# WG-JW-MB.net
KiCad netlist of a schematic drawn in Altium Designer
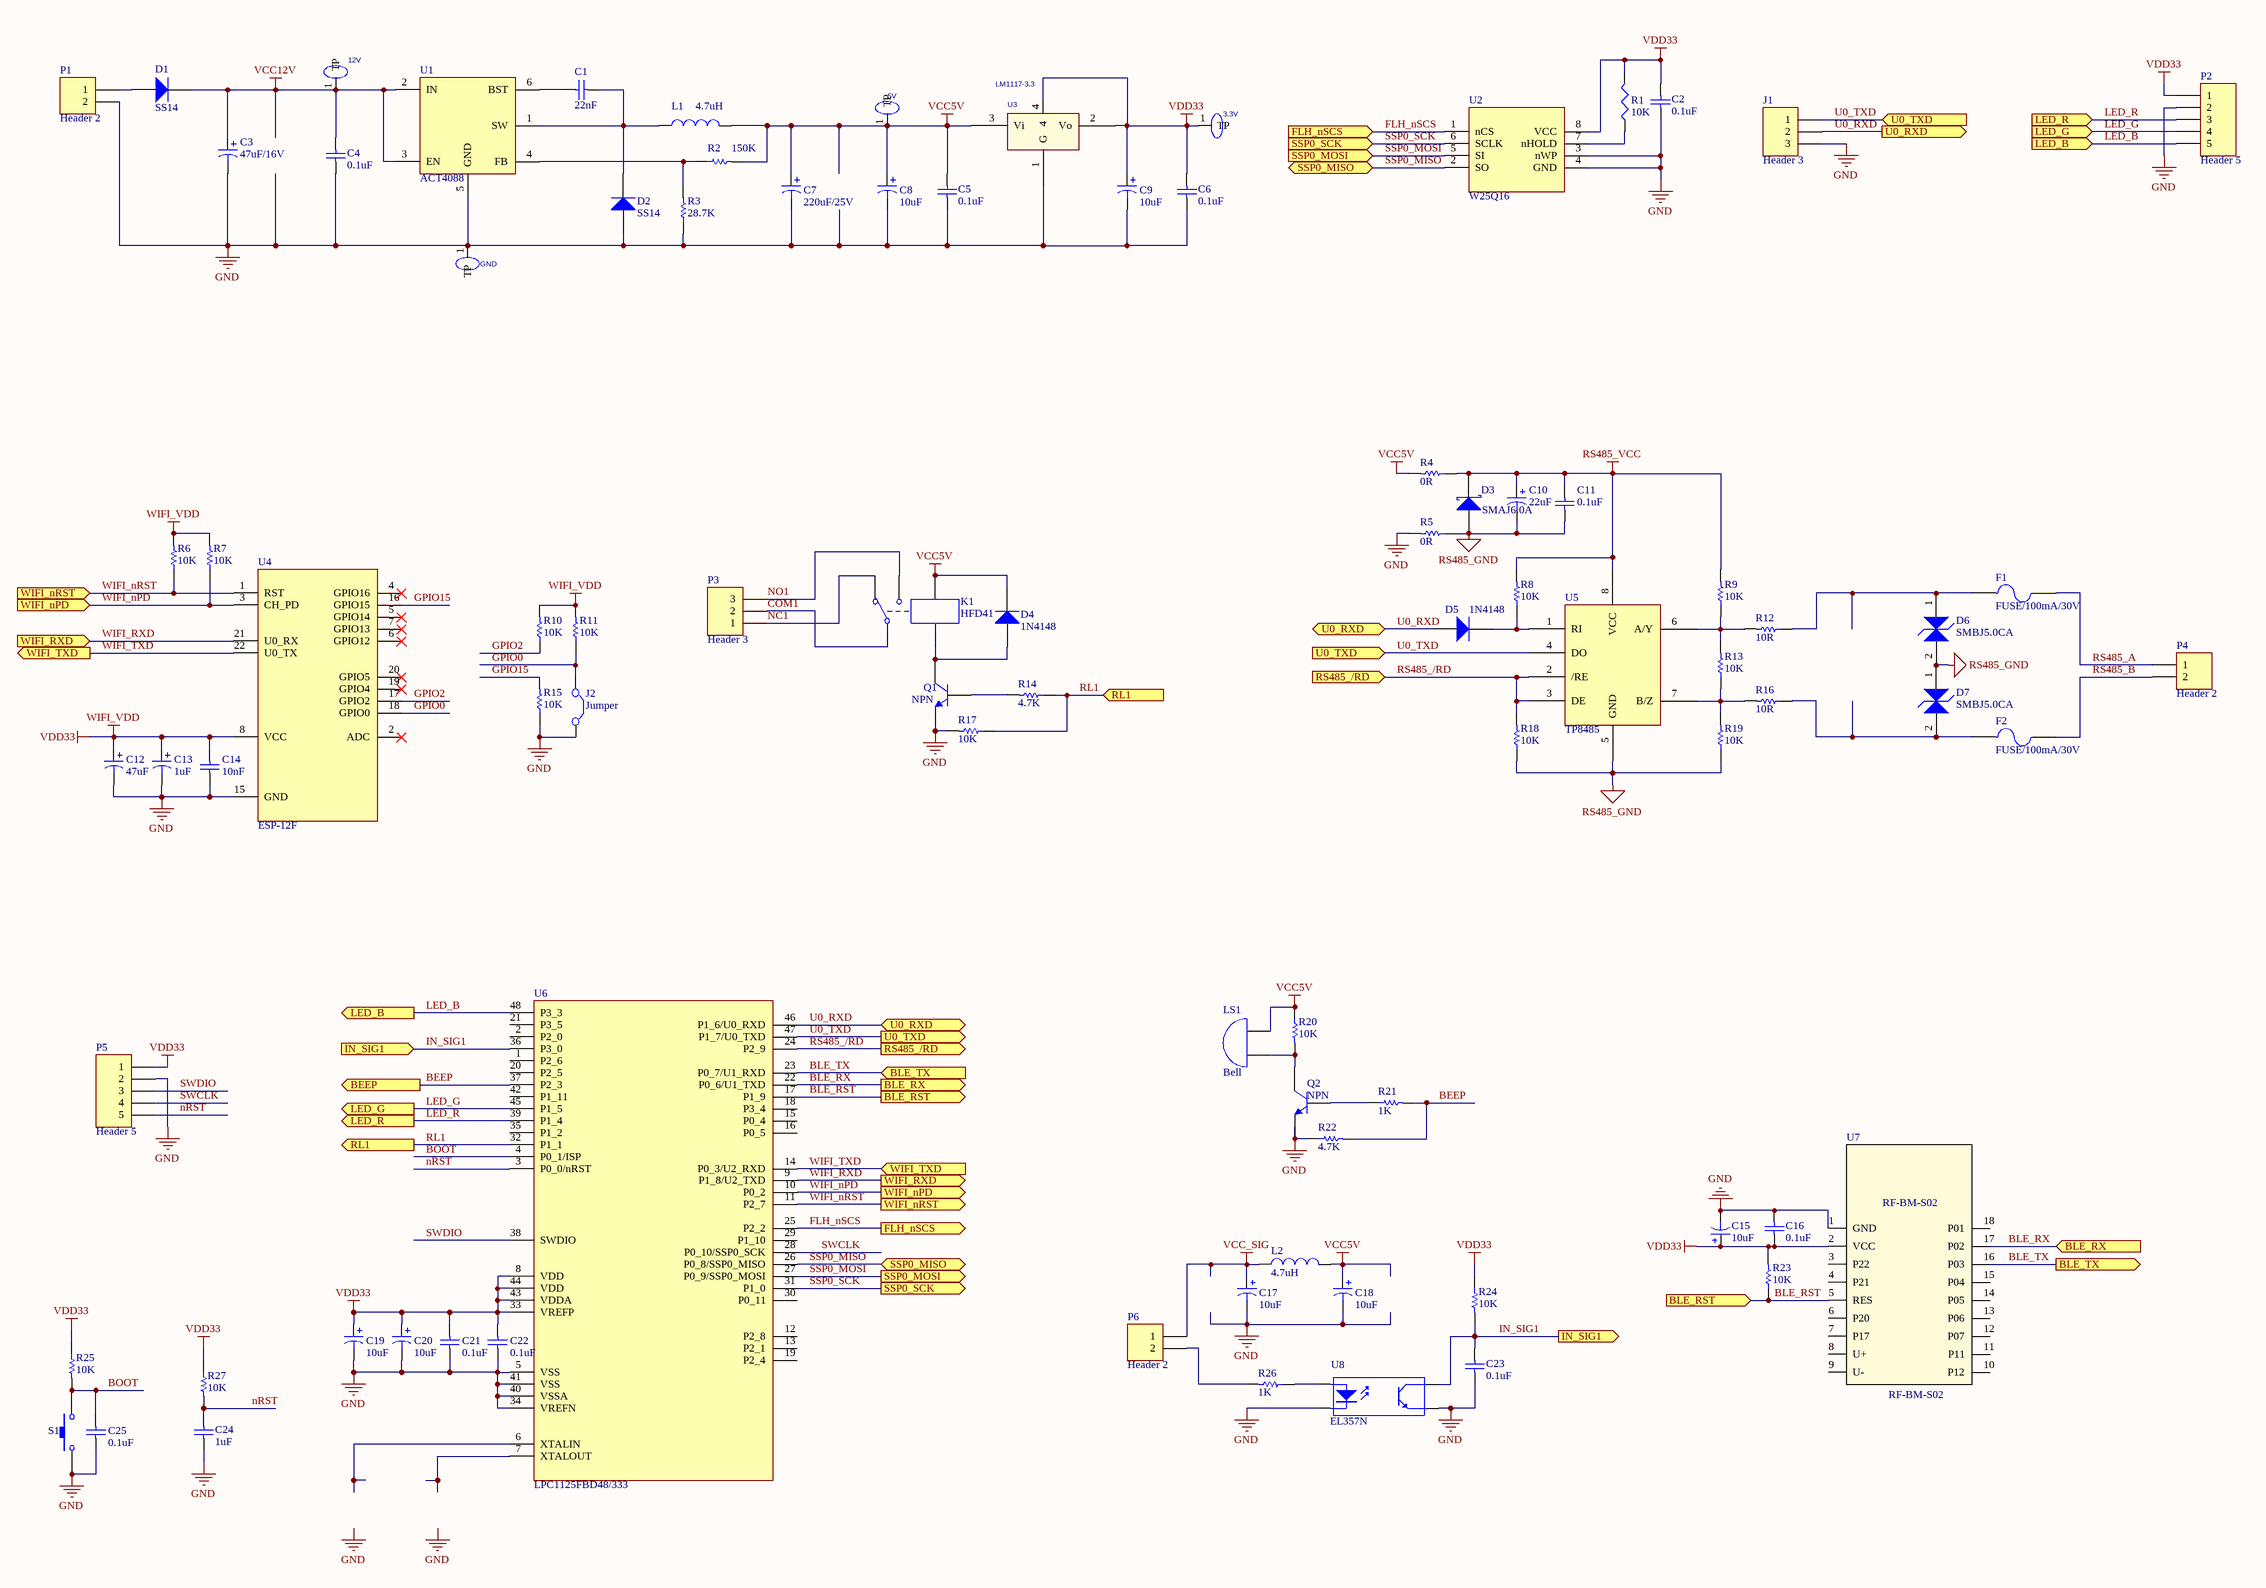
[diagram p0: WG-JW-MB.SchDoc]

(export (version "E")
  (design (tool "Eeschema 10.0.6"))
  (components
    (comp (ref "3.3V") (value "5VOUT") (libsource (lib "*") (part "TESTPOINT")))
    (comp (ref "5V") (value "5VOUT") (libsource (lib "*") (part "TESTPOINT")))
    (comp (ref "12V") (value "5VOUT") (libsource (lib "*") (part "TESTPOINT")))
    (comp (ref "C1")
      (value "22nF")
      (footprint "0805 - C")
      (description "Capacitor")
      (fields (field (name "PUBLISHER") "Altium Limited"))
      (libsource (lib "Miscellaneous Devices") (part "Cap"))
    )
    (comp (ref "C2")
      (value "0.1uF")
      (footprint "0805 - C")
      (description "Capacitor")
      (fields (field (name "PUBLISHER") "Altium Limited"))
      (libsource (lib "Miscellaneous Devices") (part "Cap"))
    )
    (comp (ref "C3")
      (value "47uF/16V")
      (footprint "smd_ec_d5.2")
      (description "Polarized Capacitor (Radial)")
      (fields (field (name "PUBLISHER") "Altium Limited"))
      (libsource (lib "Miscellaneous Devices") (part "Cap Pol1"))
    )
    (comp (ref "C4")
      (value "0.1uF")
      (footprint "0805 - C")
      (description "Capacitor")
      (fields (field (name "PUBLISHER") "Altium Limited"))
      (libsource (lib "Miscellaneous Devices") (part "Cap"))
    )
    (comp (ref "C5")
      (value "0.1uF")
      (footprint "0805 - C")
      (description "Capacitor")
      (fields (field (name "PUBLISHER") "Altium Limited"))
      (libsource (lib "Miscellaneous Devices") (part "Cap"))
    )
    (comp (ref "C6")
      (value "0.1uF")
      (footprint "0805 - C")
      (description "Capacitor")
      (fields (field (name "PUBLISHER") "Altium Limited"))
      (libsource (lib "Miscellaneous Devices") (part "Cap"))
    )
    (comp (ref "C7")
      (value "220uF/25V")
      (footprint "smd_ec_d8")
      (description "Polarized Capacitor (Radial)")
      (fields (field (name "PUBLISHER") "Altium Limited"))
      (libsource (lib "Miscellaneous Devices") (part "Cap Pol1"))
    )
    (comp (ref "C8")
      (value "10uF")
      (footprint "0805 - C")
      (description "Polarized Capacitor (Radial)")
      (fields (field (name "PUBLISHER") "Altium Limited"))
      (libsource (lib "Miscellaneous Devices") (part "Cap Pol1"))
    )
    (comp (ref "C9")
      (value "10uF")
      (footprint "0805 - C")
      (description "Polarized Capacitor (Radial)")
      (fields (field (name "PUBLISHER") "Altium Limited"))
      (libsource (lib "Miscellaneous Devices") (part "Cap Pol1"))
    )
    (comp (ref "C10")
      (value "22uF")
      (footprint "0805 - C")
      (description "Polarized Capacitor (Radial)")
      (fields (field (name "PUBLISHER") "Altium Limited"))
      (libsource (lib "Miscellaneous Devices") (part "Cap Pol1"))
    )
    (comp (ref "C11")
      (value "0.1uF")
      (footprint "0805 - C")
      (description "Capacitor")
      (fields (field (name "PUBLISHER") "Altium Limited"))
      (libsource (lib "Miscellaneous Devices") (part "Cap"))
    )
    (comp (ref "C12")
      (value "47uF")
      (footprint "SMD_EC_D5.2")
      (description "Polarized Capacitor (Radial)")
      (fields (field (name "PUBLISHER") "Altium Limited"))
      (libsource (lib "Miscellaneous Devices") (part "Cap Pol1"))
    )
    (comp (ref "C13")
      (value "1uF")
      (footprint "0805 - C")
      (description "Polarized Capacitor (Radial)")
      (fields (field (name "PUBLISHER") "Altium Limited"))
      (libsource (lib "Miscellaneous Devices") (part "Cap Pol1"))
    )
    (comp (ref "C14")
      (value "10nF")
      (footprint "0805 - C")
      (description "Capacitor")
      (fields (field (name "PUBLISHER") "Altium Limited"))
      (libsource (lib "Miscellaneous Devices") (part "Cap"))
    )
    (comp (ref "C15")
      (value "10uF")
      (footprint "0805 - C")
      (description "Polarized Capacitor (Radial)")
      (fields (field (name "PUBLISHER") "Altium Limited"))
      (libsource (lib "Miscellaneous Devices") (part "Cap Pol1"))
    )
    (comp (ref "C16")
      (value "0.1uF")
      (footprint "0805 - C")
      (description "Capacitor")
      (fields (field (name "PUBLISHER") "Altium Limited"))
      (libsource (lib "Miscellaneous Devices") (part "Cap"))
    )
    (comp (ref "C17")
      (value "10uF")
      (footprint "0805 - C")
      (description "Polarized Capacitor (Radial)")
      (fields (field (name "PUBLISHER") "Altium Limited"))
      (libsource (lib "Miscellaneous Devices") (part "Cap Pol1"))
    )
    (comp (ref "C18")
      (value "10uF")
      (footprint "0805 - C")
      (description "Polarized Capacitor (Radial)")
      (fields (field (name "PUBLISHER") "Altium Limited"))
      (libsource (lib "Miscellaneous Devices") (part "Cap Pol1"))
    )
    (comp (ref "C19")
      (value "10uF")
      (footprint "0805 - C")
      (description "Polarized Capacitor (Radial)")
      (fields (field (name "PUBLISHER") "Altium Limited"))
      (libsource (lib "Miscellaneous Devices") (part "Cap Pol1"))
    )
    (comp (ref "C20")
      (value "10uF")
      (footprint "0805 - C")
      (description "Polarized Capacitor (Radial)")
      (fields (field (name "PUBLISHER") "Altium Limited"))
      (libsource (lib "Miscellaneous Devices") (part "Cap Pol1"))
    )
    (comp (ref "C21")
      (value "0.1uF")
      (footprint "0805 - C")
      (description "Capacitor")
      (fields (field (name "PUBLISHER") "Altium Limited"))
      (libsource (lib "Miscellaneous Devices") (part "Cap"))
    )
    (comp (ref "C22")
      (value "0.1uF")
      (footprint "0805 - C")
      (description "Capacitor")
      (fields (field (name "PUBLISHER") "Altium Limited"))
      (libsource (lib "Miscellaneous Devices") (part "Cap"))
    )
    (comp (ref "C23")
      (value "0.1uF")
      (footprint "0805 - C")
      (description "Capacitor")
      (fields (field (name "PUBLISHER") "Altium Limited"))
      (libsource (lib "Miscellaneous Devices") (part "Cap"))
    )
    (comp (ref "C24")
      (value "1uF")
      (footprint "0805 - C")
      (description "Capacitor")
      (fields (field (name "PUBLISHER") "Altium Limited"))
      (libsource (lib "Miscellaneous Devices") (part "Cap"))
    )
    (comp (ref "C25")
      (value "0.1uF")
      (footprint "0805 - C")
      (description "Capacitor")
      (fields (field (name "PUBLISHER") "Altium Limited"))
      (libsource (lib "Miscellaneous Devices") (part "Cap"))
    )
    (comp (ref "D1")
      (value "SS14")
      (footprint "SMD_DIODE_SMA")
      (description "Default Diode")
      (fields (field (name "PUBLISHER") "Altium Limited"))
      (libsource (lib "Miscellaneous Devices") (part "Diode"))
    )
    (comp (ref "D2")
      (value "SS14")
      (footprint "SMD_DIODE_SMA")
      (description "Default Diode")
      (fields (field (name "PUBLISHER") "Altium Limited"))
      (libsource (lib "Miscellaneous Devices") (part "Diode"))
    )
    (comp (ref "D3")
      (value "SMAJ6.0A")
      (footprint "SMAJ_A")
      (description "Schottky Diode")
      (fields (field (name "PUBLISHER") "Altium Limited"))
      (libsource (lib "Miscellaneous Devices") (part "D Schottky"))
    )
    (comp (ref "D4")
      (value "1N4148")
      (footprint "1n4148")
      (description "Default Diode")
      (fields (field (name "PUBLISHER") "Altium Limited"))
      (libsource (lib "Miscellaneous Devices") (part "Diode"))
    )
    (comp (ref "D5")
      (value "1N4148")
      (footprint "1n4148")
      (description "Default Diode")
      (fields (field (name "PUBLISHER") "Altium Limited"))
      (libsource (lib "Miscellaneous Devices") (part "Diode"))
    )
    (comp (ref "D6") (value "SMBJ5.0CA") (footprint "SMBJ_CA") (libsource (lib "Gsd") (part "TVS")))
    (comp (ref "D7") (value "SMBJ5.0CA") (footprint "SMBJ_CA") (libsource (lib "Gsd") (part "TVS")))
    (comp (ref "F1")
      (value "FUSE/100mA/30V")
      (footprint "SMD_POLYSWITCH")
      (description "Fuse")
      (fields (field (name "PUBLISHER") "Altium Limited"))
      (libsource (lib "Miscellaneous Devices") (part "Fuse 2"))
    )
    (comp (ref "F2")
      (value "FUSE/100mA/30V")
      (footprint "SMD_POLYSWITCH")
      (description "Fuse")
      (fields (field (name "PUBLISHER") "Altium Limited"))
      (libsource (lib "Miscellaneous Devices") (part "Fuse 2"))
    )
    (comp (ref "GND") (value "5VOUT") (libsource (lib "*") (part "TESTPOINT")))
    (comp (ref "J1")
      (value "Header 3")
      (footprint "HDR1X3")
      (description "Header, 3-Pin")
      (fields (field (name "PUBLISHER") "Altium Limited"))
      (libsource (lib "Miscellaneous Connectors") (part "Header 3"))
    )
    (comp (ref "J2")
      (value "Jumper")
      (footprint "HDR1X2")
      (description "Jumper Wire")
      (fields (field (name "PUBLISHER") "Altium Limited"))
      (libsource (lib "Miscellaneous Devices") (part "Jumper"))
    )
    (comp (ref "K1")
      (value "HFD41")
      (footprint "HFD23")
      (description "Single-Pole Dual-Throw Relay")
      (fields (field (name "PUBLISHER") "Altium Limited"))
      (libsource (lib "Miscellaneous Devices") (part "Relay-SPDT"))
    )
    (comp (ref "L1")
      (value "4.7uH")
      (footprint "SMD_L_3015")
      (description "Inductor")
      (fields (field (name "PUBLISHER") "Altium Limited"))
      (libsource (lib "Miscellaneous Devices") (part "Inductor"))
    )
    (comp (ref "L2")
      (value "4.7uH")
      (footprint "SMD_L_3015")
      (description "Inductor")
      (fields (field (name "PUBLISHER") "Altium Limited"))
      (libsource (lib "Miscellaneous Devices") (part "Inductor"))
    )
    (comp (ref "LS1")
      (value "Bell")
      (footprint "BZ_D12")
      (description "Electrical Bell")
      (fields (field (name "PUBLISHER") "Altium Limited"))
      (libsource (lib "Miscellaneous Devices") (part "Bell"))
    )
    (comp (ref "P1")
      (value "Header 2")
      (footprint "CON2-5.08")
      (description "Header, 2-Pin")
      (fields (field (name "PUBLISHER") "Altium Limited"))
      (libsource (lib "") (part "Header 2_1"))
    )
    (comp (ref "P2")
      (value "Header 5")
      (footprint "CN_1X5_P200")
      (description "Header, 5-Pin")
      (fields (field (name "PUBLISHER") "Altium Limited"))
      (libsource (lib "") (part "Header 5_1"))
    )
    (comp (ref "P3")
      (value "Header 3")
      (footprint "CN_1X3_P200")
      (description "Header, 3-Pin")
      (fields (field (name "PUBLISHER") "Altium Limited"))
      (libsource (lib "") (part "Header 3_1"))
    )
    (comp (ref "P4")
      (value "Header 2")
      (footprint "cn_1x2_p200")
      (description "Header, 2-Pin")
      (fields (field (name "PUBLISHER") "Altium Limited"))
      (libsource (lib "Miscellaneous Connectors") (part "Header 2"))
    )
    (comp (ref "P5")
      (value "Header 5")
      (footprint "CN_1X5_P200")
      (description "Header, 5-Pin")
      (fields (field (name "PUBLISHER") "Altium Limited"))
      (libsource (lib "Miscellaneous Connectors") (part "Header 5"))
    )
    (comp (ref "P6")
      (value "Header 2")
      (footprint "CN_1X2_P200")
      (description "Header, 2-Pin")
      (fields (field (name "PUBLISHER") "Altium Limited"))
      (libsource (lib "") (part "Header 2_1"))
    )
    (comp (ref "Q1")
      (value "NPN")
      (footprint "SOT23")
      (description "NPN Bipolar Transistor")
      (fields (field (name "PUBLISHER") "Altium Limited"))
      (libsource (lib "Miscellaneous Devices") (part "NPN"))
    )
    (comp (ref "Q2")
      (value "NPN")
      (footprint "SOT23")
      (description "NPN Bipolar Transistor")
      (fields (field (name "PUBLISHER") "Altium Limited"))
      (libsource (lib "Miscellaneous Devices") (part "NPN"))
    )
    (comp (ref "R1")
      (value "10K")
      (footprint "0805 - R")
      (description "Resistor")
      (fields (field (name "PUBLISHER") "Altium Limited"))
      (libsource (lib "Miscellaneous Devices") (part "Res3"))
    )
    (comp (ref "R2")
      (value "150K")
      (footprint "0805 - R")
      (description "Resistor")
      (fields (field (name "PUBLISHER") "Altium Limited"))
      (libsource (lib "Miscellaneous Devices") (part "Res1"))
    )
    (comp (ref "R3")
      (value "28.7K")
      (footprint "0805 - R")
      (description "Resistor")
      (fields (field (name "PUBLISHER") "Altium Limited"))
      (libsource (lib "Miscellaneous Devices") (part "Res1"))
    )
    (comp (ref "R4")
      (value "0R")
      (footprint "0805 - R")
      (description "Resistor")
      (fields (field (name "PUBLISHER") "Altium Limited"))
      (libsource (lib "Miscellaneous Devices") (part "Res1"))
    )
    (comp (ref "R5")
      (value "0R")
      (footprint "0805 - R")
      (description "Resistor")
      (fields (field (name "PUBLISHER") "Altium Limited"))
      (libsource (lib "Miscellaneous Devices") (part "Res1"))
    )
    (comp (ref "R6")
      (value "10K")
      (footprint "0805 - R")
      (description "Resistor")
      (fields (field (name "PUBLISHER") "Altium Limited"))
      (libsource (lib "Miscellaneous Devices") (part "Res1"))
    )
    (comp (ref "R7")
      (value "10K")
      (footprint "0805 - R")
      (description "Resistor")
      (fields (field (name "PUBLISHER") "Altium Limited"))
      (libsource (lib "Miscellaneous Devices") (part "Res1"))
    )
    (comp (ref "R8")
      (value "10K")
      (footprint "0805 - R")
      (description "Resistor")
      (fields (field (name "PUBLISHER") "Altium Limited"))
      (libsource (lib "Miscellaneous Devices") (part "Res1"))
    )
    (comp (ref "R9")
      (value "10K")
      (footprint "0805 - R")
      (description "Resistor")
      (fields (field (name "PUBLISHER") "Altium Limited"))
      (libsource (lib "Miscellaneous Devices") (part "Res1"))
    )
    (comp (ref "R10")
      (value "10K")
      (footprint "0805 - R")
      (description "Resistor")
      (fields (field (name "PUBLISHER") "Altium Limited"))
      (libsource (lib "Miscellaneous Devices") (part "Res1"))
    )
    (comp (ref "R11")
      (value "10K")
      (footprint "0805 - R")
      (description "Resistor")
      (fields (field (name "PUBLISHER") "Altium Limited"))
      (libsource (lib "Miscellaneous Devices") (part "Res1"))
    )
    (comp (ref "R12")
      (value "10R")
      (footprint "0805 - R")
      (description "Resistor")
      (fields (field (name "PUBLISHER") "Altium Limited"))
      (libsource (lib "Miscellaneous Devices") (part "Res1"))
    )
    (comp (ref "R13")
      (value "10K")
      (footprint "0805 - R")
      (description "Resistor")
      (fields (field (name "PUBLISHER") "Altium Limited"))
      (libsource (lib "Miscellaneous Devices") (part "Res1"))
    )
    (comp (ref "R14")
      (value "4.7K")
      (footprint "0805 - R")
      (description "Resistor")
      (fields (field (name "PUBLISHER") "Altium Limited"))
      (libsource (lib "Miscellaneous Devices") (part "Res1"))
    )
    (comp (ref "R15")
      (value "10K")
      (footprint "0805 - R")
      (description "Resistor")
      (fields (field (name "PUBLISHER") "Altium Limited"))
      (libsource (lib "Miscellaneous Devices") (part "Res1"))
    )
    (comp (ref "R16")
      (value "10R")
      (footprint "0805 - R")
      (description "Resistor")
      (fields (field (name "PUBLISHER") "Altium Limited"))
      (libsource (lib "Miscellaneous Devices") (part "Res1"))
    )
    (comp (ref "R17")
      (value "10K")
      (footprint "0805 - R")
      (description "Resistor")
      (fields (field (name "PUBLISHER") "Altium Limited"))
      (libsource (lib "Miscellaneous Devices") (part "Res1"))
    )
    (comp (ref "R18")
      (value "10K")
      (footprint "0805 - R")
      (description "Resistor")
      (fields (field (name "PUBLISHER") "Altium Limited"))
      (libsource (lib "Miscellaneous Devices") (part "Res1"))
    )
    (comp (ref "R19")
      (value "10K")
      (footprint "0805 - R")
      (description "Resistor")
      (fields (field (name "PUBLISHER") "Altium Limited"))
      (libsource (lib "Miscellaneous Devices") (part "Res1"))
    )
    (comp (ref "R20")
      (value "10K")
      (footprint "0805 - R")
      (description "Resistor")
      (fields (field (name "PUBLISHER") "Altium Limited"))
      (libsource (lib "Miscellaneous Devices") (part "Res1"))
    )
    (comp (ref "R21")
      (value "1K")
      (footprint "0805 - R")
      (description "Resistor")
      (fields (field (name "PUBLISHER") "Altium Limited"))
      (libsource (lib "Miscellaneous Devices") (part "Res1"))
    )
    (comp (ref "R22")
      (value "4.7K")
      (footprint "0805 - R")
      (description "Resistor")
      (fields (field (name "PUBLISHER") "Altium Limited"))
      (libsource (lib "Miscellaneous Devices") (part "Res1"))
    )
    (comp (ref "R23")
      (value "10K")
      (footprint "0805 - R")
      (description "Resistor")
      (fields (field (name "PUBLISHER") "Altium Limited"))
      (libsource (lib "Miscellaneous Devices") (part "Res1"))
    )
    (comp (ref "R24")
      (value "10K")
      (footprint "0805 - R")
      (description "Resistor")
      (fields (field (name "PUBLISHER") "Altium Limited"))
      (libsource (lib "Miscellaneous Devices") (part "Res1"))
    )
    (comp (ref "R25")
      (value "10K")
      (footprint "0805 - R")
      (description "Resistor")
      (fields (field (name "PUBLISHER") "Altium Limited"))
      (libsource (lib "Miscellaneous Devices") (part "Res1"))
    )
    (comp (ref "R26")
      (value "1K")
      (footprint "0805 - R")
      (description "Resistor")
      (fields (field (name "PUBLISHER") "Altium Limited"))
      (libsource (lib "Miscellaneous Devices") (part "Res1"))
    )
    (comp (ref "R27")
      (value "10K")
      (footprint "0805 - R")
      (description "Resistor")
      (fields (field (name "PUBLISHER") "Altium Limited"))
      (libsource (lib "Miscellaneous Devices") (part "Res1"))
    )
    (comp (ref "S1")
      (value "SW-PB")
      (footprint "SW_SMD_2P")
      (description "Switch")
      (fields (field (name "PUBLISHER") "Altium Limited"))
      (libsource (lib "Miscellaneous Devices") (part "SW-PB"))
    )
    (comp (ref "U1") (value "ACT4088") (footprint "SOT23-6") (libsource (lib "Gsd") (part "ACT4088")))
    (comp (ref "U2") (value "W25Q16") (footprint "SOIC8-50X204") (libsource (lib "Gsd") (part "MX25Lxx")))
    (comp (ref "U3") (value "LM1117-3.3") (libsource (lib "*") (part "LM1117_1")))
    (comp (ref "U4") (value "ESP-12F") (footprint "WIFI-ESP") (libsource (lib "Gsd") (part "ESP-12F")))
    (comp (ref "U5") (value "TP8485") (footprint "SOIC8-50X204") (libsource (lib "Gsd") (part "TP8485")))
    (comp (ref "U6")
      (value "LPC1125FBD48/333")
      (footprint "TQFP48")
      (libsource (lib "Gsd") (part "LPC1125FBD48/333"))
    )
    (comp (ref "U7")
      (value "RF-BM-S02")
      (footprint "RF-BM-S02")
      (libsource (lib "WG-LOCK") (part "RF-BM-S02"))
    )
    (comp (ref "U8")
      (value "EL357N")
      (footprint "SOP4")
      (description "4-Pin Phototransistor Optocoupler")
      (fields (field (name "PUBLISHER") "Altium Limited"))
      (libsource (lib "Miscellaneous Devices") (part "Optoisolator1"))
    )
  )
  (nets
    (net (code "1") (name "/BEEP") (class "Default")
      (node (ref "R21") (pin "2") (pinfunction "2_2") (pintype "passive"))
      (node (ref "R22") (pin "2") (pinfunction "2_2") (pintype "passive"))
      (node (ref "U6") (pin "37") (pinfunction "P2_3_37") (pintype "passive"))
    )
    (net (code "2") (name "/BLE_RST") (class "Default")
      (node (ref "R23") (pin "1") (pinfunction "1_1") (pintype "passive"))
      (node (ref "U6") (pin "17") (pinfunction "P1_9_17") (pintype "passive"))
      (node (ref "U7") (pin "5") (pinfunction "RES_5") (pintype "passive"))
    )
    (net (code "3") (name "/BLE_RX") (class "Default")
      (node (ref "U6") (pin "22") (pinfunction "P0_6/U1_TXD_22") (pintype "passive"))
      (node (ref "U7") (pin "17") (pinfunction "P02_17") (pintype "passive"))
    )
    (net (code "4") (name "/BLE_TX") (class "Default")
      (node (ref "U6") (pin "23") (pinfunction "P0_7/U1_RXD_23") (pintype "passive"))
      (node (ref "U7") (pin "16") (pinfunction "P03_16") (pintype "passive"))
    )
    (net (code "5") (name "/BOOT") (class "Default")
      (node (ref "C25") (pin "2") (pinfunction "2_2") (pintype "passive"))
      (node (ref "R25") (pin "2") (pinfunction "2_2") (pintype "passive"))
      (node (ref "S1") (pin "2") (pinfunction "2_2") (pintype "passive"))
      (node (ref "U6") (pin "4") (pinfunction "P0_1/ISP_4") (pintype "passive"))
    )
    (net (code "6") (name "/COM1") (class "Default")
      (node (ref "K1") (pin "1") (pinfunction "1_1") (pintype "passive"))
      (node (ref "P3") (pin "2") (pinfunction "2_2") (pintype "passive"))
    )
    (net (code "7") (name "/FLH_nSCS") (class "Default")
      (node (ref "U2") (pin "1") (pinfunction "nCS_1") (pintype "passive"))
      (node (ref "U6") (pin "25") (pinfunction "P2_2_25") (pintype "passive"))
    )
    (net (code "8") (name "/GPIO0") (class "Default")
      (node (ref "J2") (pin "1") (pinfunction "C1_1") (pintype "passive"))
      (node (ref "R11") (pin "1") (pinfunction "1_1") (pintype "passive"))
      (node (ref "U4") (pin "18") (pinfunction "GPIO0_18") (pintype "passive"))
    )
    (net (code "9") (name "/GPIO2") (class "Default")
      (node (ref "R10") (pin "1") (pinfunction "1_1") (pintype "passive"))
      (node (ref "U4") (pin "17") (pinfunction "GPIO2_17") (pintype "passive"))
    )
    (net (code "10") (name "/GPIO15") (class "Default")
      (node (ref "R15") (pin "2") (pinfunction "2_2") (pintype "passive"))
      (node (ref "U4") (pin "16") (pinfunction "GPIO15_16") (pintype "passive"))
    )
    (net (code "11") (name "/IN_SIG1") (class "Default")
      (node (ref "C23") (pin "2") (pinfunction "2_2") (pintype "passive"))
      (node (ref "R24") (pin "2") (pinfunction "2_2") (pintype "passive"))
      (node (ref "U6") (pin "36") (pinfunction "P3_0_36") (pintype "passive"))
      (node (ref "U8") (pin "4") (pinfunction "C_4") (pintype "passive"))
    )
    (net (code "12") (name "/LED_B") (class "Default")
      (node (ref "P2") (pin "5") (pinfunction "5_5") (pintype "passive"))
      (node (ref "U6") (pin "48") (pinfunction "P3_3_48") (pintype "passive"))
    )
    (net (code "13") (name "/LED_G") (class "Default")
      (node (ref "P2") (pin "4") (pinfunction "4_4") (pintype "passive"))
      (node (ref "U6") (pin "45") (pinfunction "P1_5_45") (pintype "passive"))
    )
    (net (code "14") (name "/LED_R") (class "Default")
      (node (ref "P2") (pin "3") (pinfunction "3_3") (pintype "passive"))
      (node (ref "U6") (pin "39") (pinfunction "P1_4_39") (pintype "passive"))
    )
    (net (code "15") (name "/NC1") (class "Default")
      (node (ref "K1") (pin "2") (pinfunction "2_2") (pintype "passive"))
      (node (ref "P3") (pin "1") (pinfunction "1_1") (pintype "passive"))
    )
    (net (code "16") (name "/NO1") (class "Default")
      (node (ref "K1") (pin "3") (pinfunction "3_3") (pintype "passive"))
      (node (ref "P3") (pin "3") (pinfunction "3_3") (pintype "passive"))
    )
    (net (code "17") (name "/RL1") (class "Default")
      (node (ref "R14") (pin "1") (pinfunction "1_1") (pintype "passive"))
      (node (ref "R17") (pin "1") (pinfunction "1_1") (pintype "passive"))
      (node (ref "U6") (pin "32") (pinfunction "P1_1_32") (pintype "passive"))
    )
    (net (code "18") (name "/RS485_A") (class "Default")
      (node (ref "F1") (pin "2") (pinfunction "2_2") (pintype "passive"))
      (node (ref "P4") (pin "1") (pinfunction "1_1") (pintype "passive"))
    )
    (net (code "19") (name "/RS485_B") (class "Default")
      (node (ref "F2") (pin "2") (pinfunction "2_2") (pintype "passive"))
      (node (ref "P4") (pin "2") (pinfunction "2_2") (pintype "passive"))
    )
    (net (code "20") (name "/RS485_{slash}RD") (class "Default")
      (node (ref "R18") (pin "2") (pinfunction "2_2") (pintype "passive"))
      (node (ref "U5") (pin "2") (pinfunction "/RE_2") (pintype "passive"))
      (node (ref "U5") (pin "3") (pinfunction "DE_3") (pintype "passive"))
      (node (ref "U6") (pin "24") (pinfunction "P2_9_24") (pintype "passive"))
    )
    (net (code "21") (name "/SSP0_MISO") (class "Default")
      (node (ref "U2") (pin "2") (pinfunction "SO_2") (pintype "passive"))
      (node (ref "U6") (pin "26") (pinfunction "P0_8/SSP0_MISO_26") (pintype "passive"))
    )
    (net (code "22") (name "/SSP0_MOSI") (class "Default")
      (node (ref "U2") (pin "5") (pinfunction "SI_5") (pintype "passive"))
      (node (ref "U6") (pin "27") (pinfunction "P0_9/SSP0_MOSI_27") (pintype "passive"))
    )
    (net (code "23") (name "/SSP0_SCK") (class "Default")
      (node (ref "U2") (pin "6") (pinfunction "SCLK_6") (pintype "passive"))
      (node (ref "U6") (pin "31") (pinfunction "P1_0_31") (pintype "passive"))
    )
    (net (code "24") (name "/SWCLK") (class "Default")
      (node (ref "P5") (pin "4") (pinfunction "4_4") (pintype "passive"))
      (node (ref "U6") (pin "28") (pinfunction "P0_10/SSP0_SCK_28") (pintype "passive"))
    )
    (net (code "25") (name "/SWDIO") (class "Default")
      (node (ref "P5") (pin "3") (pinfunction "3_3") (pintype "passive"))
      (node (ref "U6") (pin "38") (pinfunction "SWDIO_38") (pintype "passive"))
    )
    (net (code "26") (name "/U0_RXD") (class "Default")
      (node (ref "D5") (pin "1") (pinfunction "A_1") (pintype "passive"))
      (node (ref "J1") (pin "2") (pinfunction "2_2") (pintype "passive"))
      (node (ref "U6") (pin "46") (pinfunction "P1_6/U0_RXD_46") (pintype "passive"))
    )
    (net (code "27") (name "/U0_TXD") (class "Default")
      (node (ref "J1") (pin "1") (pinfunction "1_1") (pintype "passive"))
      (node (ref "U5") (pin "4") (pinfunction "DO_4") (pintype "passive"))
      (node (ref "U6") (pin "47") (pinfunction "P1_7/U0_TXD_47") (pintype "passive"))
    )
    (net (code "28") (name "/WIFI_RXD") (class "Default")
      (node (ref "U4") (pin "21") (pinfunction "U0_RX_21") (pintype "passive"))
      (node (ref "U6") (pin "9") (pinfunction "P1_8/U2_TXD_9") (pintype "passive"))
    )
    (net (code "29") (name "/WIFI_TXD") (class "Default")
      (node (ref "U4") (pin "22") (pinfunction "U0_TX_22") (pintype "passive"))
      (node (ref "U6") (pin "14") (pinfunction "P0_3/U2_RXD_14") (pintype "passive"))
    )
    (net (code "30") (name "/WIFI_nPD") (class "Default")
      (node (ref "R7") (pin "1") (pinfunction "1_1") (pintype "passive"))
      (node (ref "U4") (pin "3") (pinfunction "CH_PD_3") (pintype "passive"))
      (node (ref "U6") (pin "10") (pinfunction "P0_2_10") (pintype "passive"))
    )
    (net (code "31") (name "/WIFI_nRST") (class "Default")
      (node (ref "R6") (pin "1") (pinfunction "1_1") (pintype "passive"))
      (node (ref "U4") (pin "1") (pinfunction "RST_1") (pintype "passive"))
      (node (ref "U6") (pin "11") (pinfunction "P2_7_11") (pintype "passive"))
    )
    (net (code "32") (name "/nRST") (class "Default")
      (node (ref "C24") (pin "2") (pinfunction "2_2") (pintype "passive"))
      (node (ref "P5") (pin "5") (pinfunction "5_5") (pintype "passive"))
      (node (ref "R27") (pin "2") (pinfunction "2_2") (pintype "passive"))
      (node (ref "U6") (pin "3") (pinfunction "P0_0/nRST_3") (pintype "passive"))
    )
    (net (code "33") (name "GND") (class "Default")
      (node (ref "C12") (pin "2") (pinfunction "2_2") (pintype "passive"))
      (node (ref "C13") (pin "2") (pinfunction "2_2") (pintype "passive"))
      (node (ref "C14") (pin "1") (pinfunction "1_1") (pintype "passive"))
      (node (ref "C15") (pin "2") (pinfunction "2_2") (pintype "passive"))
      (node (ref "C16") (pin "2") (pinfunction "2_2") (pintype "passive"))
      (node (ref "C17") (pin "2") (pinfunction "2_2") (pintype "passive"))
      (node (ref "C18") (pin "2") (pinfunction "2_2") (pintype "passive"))
      (node (ref "C19") (pin "2") (pinfunction "2_2") (pintype "passive"))
      (node (ref "C2") (pin "1") (pinfunction "1_1") (pintype "passive"))
      (node (ref "C20") (pin "2") (pinfunction "2_2") (pintype "passive"))
      (node (ref "C21") (pin "1") (pinfunction "1_1") (pintype "passive"))
      (node (ref "C22") (pin "1") (pinfunction "1_1") (pintype "passive"))
      (node (ref "C23") (pin "1") (pinfunction "1_1") (pintype "passive"))
      (node (ref "C24") (pin "1") (pinfunction "1_1") (pintype "passive"))
      (node (ref "C25") (pin "1") (pinfunction "1_1") (pintype "passive"))
      (node (ref "C3") (pin "2") (pinfunction "2_2") (pintype "passive"))
      (node (ref "C4") (pin "1") (pinfunction "1_1") (pintype "passive"))
      (node (ref "C5") (pin "1") (pinfunction "1_1") (pintype "passive"))
      (node (ref "C6") (pin "1") (pinfunction "1_1") (pintype "passive"))
      (node (ref "C7") (pin "2") (pinfunction "2_2") (pintype "passive"))
      (node (ref "C8") (pin "2") (pinfunction "2_2") (pintype "passive"))
      (node (ref "C9") (pin "2") (pinfunction "2_2") (pintype "passive"))
      (node (ref "D2") (pin "1") (pinfunction "A_1") (pintype "passive"))
      (node (ref "GND") (pin "1") (pinfunction "TP_1") (pintype "passive"))
      (node (ref "J1") (pin "3") (pinfunction "3_3") (pintype "passive"))
      (node (ref "J2") (pin "2") (pinfunction "C2_2") (pintype "passive"))
      (node (ref "P1") (pin "2") (pinfunction "2_2") (pintype "passive"))
      (node (ref "P2") (pin "2") (pinfunction "2_2") (pintype "passive"))
      (node (ref "P5") (pin "2") (pinfunction "2_2") (pintype "passive"))
      (node (ref "Q1") (pin "3") (pinfunction "E_3") (pintype "passive"))
      (node (ref "Q2") (pin "3") (pinfunction "E_3") (pintype "passive"))
      (node (ref "R15") (pin "1") (pinfunction "1_1") (pintype "passive"))
      (node (ref "R17") (pin "2") (pinfunction "2_2") (pintype "passive"))
      (node (ref "R22") (pin "1") (pinfunction "1_1") (pintype "passive"))
      (node (ref "R3") (pin "1") (pinfunction "1_1") (pintype "passive"))
      (node (ref "R5") (pin "2") (pinfunction "2_2") (pintype "passive"))
      (node (ref "S1") (pin "1") (pinfunction "1_1") (pintype "passive"))
      (node (ref "U1") (pin "5") (pinfunction "GND_5") (pintype "passive"))
      (node (ref "U2") (pin "3") (pinfunction "nWP_3") (pintype "passive"))
      (node (ref "U2") (pin "4") (pinfunction "GND_4") (pintype "passive"))
      (node (ref "U3") (pin "1") (pinfunction "G_1") (pintype "passive"))
      (node (ref "U4") (pin "15") (pinfunction "GND_15") (pintype "passive"))
      (node (ref "U6") (pin "34") (pinfunction "VREFN_34") (pintype "passive"))
      (node (ref "U6") (pin "40") (pinfunction "VSSA_40") (pintype "passive"))
      (node (ref "U6") (pin "41") (pinfunction "VSS_41") (pintype "passive"))
      (node (ref "U6") (pin "5") (pinfunction "VSS_5") (pintype "passive"))
      (node (ref "U7") (pin "1") (pinfunction "GND_1") (pintype "passive"))
      (node (ref "U8") (pin "2") (pinfunction "K_2") (pintype "passive"))
      (node (ref "U8") (pin "3") (pinfunction "E_3") (pintype "passive"))
    )
    (net (code "34") (name "Net-(D1-A)") (class "Default")
      (node (ref "D1") (pin "1") (pinfunction "A_1") (pintype "passive"))
      (node (ref "P1") (pin "1") (pinfunction "1_1") (pintype "passive"))
    )
    (net (code "35") (name "Net-(D2-K)") (class "Default")
      (node (ref "C1") (pin "1") (pinfunction "1_1") (pintype "passive"))
      (node (ref "D2") (pin "2") (pinfunction "K_2") (pintype "passive"))
      (node (ref "L1") (pin "1") (pinfunction "1_1") (pintype "passive"))
      (node (ref "U1") (pin "1") (pinfunction "SW_1") (pintype "passive"))
    )
    (net (code "36") (name "Net-(D4-A)") (class "Default")
      (node (ref "D4") (pin "1") (pinfunction "A_1") (pintype "passive"))
      (node (ref "K1") (pin "4") (pinfunction "4_4") (pintype "passive"))
      (node (ref "Q1") (pin "1") (pinfunction "C_1") (pintype "passive"))
    )
    (net (code "37") (name "Net-(D5-K)") (class "Default")
      (node (ref "D5") (pin "2") (pinfunction "K_2") (pintype "passive"))
      (node (ref "R8") (pin "1") (pinfunction "1_1") (pintype "passive"))
      (node (ref "U5") (pin "1") (pinfunction "RI_1") (pintype "passive"))
    )
    (net (code "38") (name "Net-(D6-Pad1)") (class "Default")
      (node (ref "D6") (pin "1") (pinfunction "1_1") (pintype "passive"))
      (node (ref "F1") (pin "1") (pinfunction "1_1") (pintype "passive"))
      (node (ref "R12") (pin "1") (pinfunction "1_1") (pintype "passive"))
    )
    (net (code "39") (name "Net-(D7-Pad2)") (class "Default")
      (node (ref "D7") (pin "2") (pinfunction "2_2") (pintype "passive"))
      (node (ref "F2") (pin "1") (pinfunction "1_1") (pintype "passive"))
      (node (ref "R16") (pin "1") (pinfunction "1_1") (pintype "passive"))
    )
    (net (code "40") (name "Net-(LS1-B)") (class "Default")
      (node (ref "LS1") (pin "2") (pinfunction "B_2") (pintype "passive"))
      (node (ref "Q2") (pin "1") (pinfunction "C_1") (pintype "passive"))
      (node (ref "R20") (pin "2") (pinfunction "2_2") (pintype "passive"))
    )
    (net (code "41") (name "Net-(P6-Pad2)") (class "Default")
      (node (ref "P6") (pin "2") (pinfunction "2_2") (pintype "passive"))
      (node (ref "R26") (pin "2") (pinfunction "2_2") (pintype "passive"))
    )
    (net (code "42") (name "Net-(Q1-B)") (class "Default")
      (node (ref "Q1") (pin "2") (pinfunction "B_2") (pintype "passive"))
      (node (ref "R14") (pin "2") (pinfunction "2_2") (pintype "passive"))
    )
    (net (code "43") (name "Net-(Q2-B)") (class "Default")
      (node (ref "Q2") (pin "2") (pinfunction "B_2") (pintype "passive"))
      (node (ref "R21") (pin "1") (pinfunction "1_1") (pintype "passive"))
    )
    (net (code "44") (name "Net-(U1-BST)") (class "Default")
      (node (ref "C1") (pin "2") (pinfunction "2_2") (pintype "passive"))
      (node (ref "U1") (pin "6") (pinfunction "BST_6") (pintype "passive"))
    )
    (net (code "45") (name "Net-(U1-FB)") (class "Default")
      (node (ref "R2") (pin "1") (pinfunction "1_1") (pintype "passive"))
      (node (ref "R3") (pin "2") (pinfunction "2_2") (pintype "passive"))
      (node (ref "U1") (pin "4") (pinfunction "FB_4") (pintype "passive"))
    )
    (net (code "46") (name "Net-(U2-nHOLD)") (class "Default")
      (node (ref "R1") (pin "1") (pinfunction "1_1") (pintype "passive"))
      (node (ref "U2") (pin "7") (pinfunction "nHOLD_7") (pintype "passive"))
    )
    (net (code "47") (name "Net-(U5-A{slash}Y)") (class "Default")
      (node (ref "R12") (pin "2") (pinfunction "2_2") (pintype "passive"))
      (node (ref "R13") (pin "2") (pinfunction "2_2") (pintype "passive"))
      (node (ref "R9") (pin "1") (pinfunction "1_1") (pintype "passive"))
      (node (ref "U5") (pin "6") (pinfunction "A/Y_6") (pintype "passive"))
    )
    (net (code "48") (name "Net-(U5-B{slash}Z)") (class "Default")
      (node (ref "R13") (pin "1") (pinfunction "1_1") (pintype "passive"))
      (node (ref "R16") (pin "2") (pinfunction "2_2") (pintype "passive"))
      (node (ref "R19") (pin "2") (pinfunction "2_2") (pintype "passive"))
      (node (ref "U5") (pin "7") (pinfunction "B/Z_7") (pintype "passive"))
    )
    (net (code "49") (name "Net-(U8-A)") (class "Default")
      (node (ref "R26") (pin "1") (pinfunction "1_1") (pintype "passive"))
      (node (ref "U8") (pin "1") (pinfunction "A_1") (pintype "passive"))
    )
    (net (code "50") (name "RS485_GND") (class "Default")
      (node (ref "C10") (pin "2") (pinfunction "2_2") (pintype "passive"))
      (node (ref "C11") (pin "2") (pinfunction "2_2") (pintype "passive"))
      (node (ref "D3") (pin "1") (pinfunction "A_1") (pintype "passive"))
      (node (ref "D6") (pin "2") (pinfunction "2_2") (pintype "passive"))
      (node (ref "D7") (pin "1") (pinfunction "1_1") (pintype "passive"))
      (node (ref "R18") (pin "1") (pinfunction "1_1") (pintype "passive"))
      (node (ref "R19") (pin "1") (pinfunction "1_1") (pintype "passive"))
      (node (ref "R5") (pin "1") (pinfunction "1_1") (pintype "passive"))
      (node (ref "U5") (pin "5") (pinfunction "GND_5") (pintype "passive"))
    )
    (net (code "51") (name "RS485_VCC") (class "Default")
      (node (ref "C10") (pin "1") (pinfunction "1_1") (pintype "passive"))
      (node (ref "C11") (pin "1") (pinfunction "1_1") (pintype "passive"))
      (node (ref "D3") (pin "2") (pinfunction "K_2") (pintype "passive"))
      (node (ref "R4") (pin "1") (pinfunction "1_1") (pintype "passive"))
      (node (ref "R8") (pin "2") (pinfunction "2_2") (pintype "passive"))
      (node (ref "R9") (pin "2") (pinfunction "2_2") (pintype "passive"))
      (node (ref "U5") (pin "8") (pinfunction "VCC_8") (pintype "passive"))
    )
    (net (code "52") (name "VCC5V") (class "Default")
      (node (ref "5V") (pin "1") (pinfunction "TP_1") (pintype "passive"))
      (node (ref "C18") (pin "1") (pinfunction "1_1") (pintype "passive"))
      (node (ref "C5") (pin "2") (pinfunction "2_2") (pintype "passive"))
      (node (ref "C7") (pin "1") (pinfunction "1_1") (pintype "passive"))
      (node (ref "C8") (pin "1") (pinfunction "1_1") (pintype "passive"))
      (node (ref "D4") (pin "2") (pinfunction "K_2") (pintype "passive"))
      (node (ref "K1") (pin "5") (pinfunction "5_5") (pintype "passive"))
      (node (ref "L1") (pin "2") (pinfunction "2_2") (pintype "passive"))
      (node (ref "L2") (pin "2") (pinfunction "2_2") (pintype "passive"))
      (node (ref "LS1") (pin "1") (pinfunction "A_1") (pintype "passive"))
      (node (ref "R2") (pin "2") (pinfunction "2_2") (pintype "passive"))
      (node (ref "R20") (pin "1") (pinfunction "1_1") (pintype "passive"))
      (node (ref "R4") (pin "2") (pinfunction "2_2") (pintype "passive"))
      (node (ref "U3") (pin "3") (pinfunction "Vi_3") (pintype "passive"))
    )
    (net (code "53") (name "VCC12V") (class "Default")
      (node (ref "12V") (pin "1") (pinfunction "TP_1") (pintype "passive"))
      (node (ref "C3") (pin "1") (pinfunction "1_1") (pintype "passive"))
      (node (ref "C4") (pin "2") (pinfunction "2_2") (pintype "passive"))
      (node (ref "D1") (pin "2") (pinfunction "K_2") (pintype "passive"))
      (node (ref "U1") (pin "2") (pinfunction "IN_2") (pintype "passive"))
      (node (ref "U1") (pin "3") (pinfunction "EN_3") (pintype "passive"))
    )
    (net (code "54") (name "VCC_SIG") (class "Default")
      (node (ref "C17") (pin "1") (pinfunction "1_1") (pintype "passive"))
      (node (ref "L2") (pin "1") (pinfunction "1_1") (pintype "passive"))
      (node (ref "P6") (pin "1") (pinfunction "1_1") (pintype "passive"))
    )
    (net (code "55") (name "VDD33") (class "Default")
      (node (ref "3.3V") (pin "1") (pinfunction "TP_1") (pintype "passive"))
      (node (ref "C12") (pin "1") (pinfunction "1_1") (pintype "passive"))
      (node (ref "C13") (pin "1") (pinfunction "1_1") (pintype "passive"))
      (node (ref "C14") (pin "2") (pinfunction "2_2") (pintype "passive"))
      (node (ref "C15") (pin "1") (pinfunction "1_1") (pintype "passive"))
      (node (ref "C16") (pin "1") (pinfunction "1_1") (pintype "passive"))
      (node (ref "C19") (pin "1") (pinfunction "1_1") (pintype "passive"))
      (node (ref "C2") (pin "2") (pinfunction "2_2") (pintype "passive"))
      (node (ref "C20") (pin "1") (pinfunction "1_1") (pintype "passive"))
      (node (ref "C21") (pin "2") (pinfunction "2_2") (pintype "passive"))
      (node (ref "C22") (pin "2") (pinfunction "2_2") (pintype "passive"))
      (node (ref "C6") (pin "2") (pinfunction "2_2") (pintype "passive"))
      (node (ref "C9") (pin "1") (pinfunction "1_1") (pintype "passive"))
      (node (ref "P2") (pin "1") (pinfunction "1_1") (pintype "passive"))
      (node (ref "P5") (pin "1") (pinfunction "1_1") (pintype "passive"))
      (node (ref "R1") (pin "2") (pinfunction "2_2") (pintype "passive"))
      (node (ref "R10") (pin "2") (pinfunction "2_2") (pintype "passive"))
      (node (ref "R11") (pin "2") (pinfunction "2_2") (pintype "passive"))
      (node (ref "R23") (pin "2") (pinfunction "2_2") (pintype "passive"))
      (node (ref "R24") (pin "1") (pinfunction "1_1") (pintype "passive"))
      (node (ref "R25") (pin "1") (pinfunction "1_1") (pintype "passive"))
      (node (ref "R27") (pin "1") (pinfunction "1_1") (pintype "passive"))
      (node (ref "R6") (pin "2") (pinfunction "2_2") (pintype "passive"))
      (node (ref "R7") (pin "2") (pinfunction "2_2") (pintype "passive"))
      (node (ref "U2") (pin "8") (pinfunction "VCC_8") (pintype "passive"))
      (node (ref "U3") (pin "2") (pinfunction "Vo_2") (pintype "passive"))
      (node (ref "U3") (pin "4") (pinfunction "4_4") (pintype "passive"))
      (node (ref "U4") (pin "8") (pinfunction "VCC_8") (pintype "passive"))
      (node (ref "U6") (pin "33") (pinfunction "VREFP_33") (pintype "passive"))
      (node (ref "U6") (pin "43") (pinfunction "VDDA_43") (pintype "passive"))
      (node (ref "U6") (pin "44") (pinfunction "VDD_44") (pintype "passive"))
      (node (ref "U6") (pin "8") (pinfunction "VDD_8") (pintype "passive"))
      (node (ref "U7") (pin "2") (pinfunction "VCC_2") (pintype "passive"))
    )
    (net (code "56") (name "unconnected-(U4-ADC-Pad2)") (class "Default")
      (node (ref "U4") (pin "2") (pinfunction "ADC_2") (pintype "passive+no_connect"))
    )
    (net (code "57") (name "unconnected-(U4-GPIO4-Pad19)") (class "Default")
      (node (ref "U4") (pin "19") (pinfunction "GPIO4_19") (pintype "passive+no_connect"))
    )
    (net (code "58") (name "unconnected-(U4-GPIO5-Pad20)") (class "Default")
      (node (ref "U4") (pin "20") (pinfunction "GPIO5_20") (pintype "passive+no_connect"))
    )
    (net (code "59") (name "unconnected-(U4-GPIO12-Pad6)") (class "Default")
      (node (ref "U4") (pin "6") (pinfunction "GPIO12_6") (pintype "passive+no_connect"))
    )
    (net (code "60") (name "unconnected-(U4-GPIO13-Pad7)") (class "Default")
      (node (ref "U4") (pin "7") (pinfunction "GPIO13_7") (pintype "passive+no_connect"))
    )
    (net (code "61") (name "unconnected-(U4-GPIO14-Pad5)") (class "Default")
      (node (ref "U4") (pin "5") (pinfunction "GPIO14_5") (pintype "passive+no_connect"))
    )
    (net (code "62") (name "unconnected-(U4-GPIO16-Pad4)") (class "Default")
      (node (ref "U4") (pin "4") (pinfunction "GPIO16_4") (pintype "passive+no_connect"))
    )
    (net (code "63") (name "unconnected-(U6-P0_4-Pad15)") (class "Default")
      (node (ref "U6") (pin "15") (pinfunction "P0_4_15") (pintype "passive"))
    )
    (net (code "64") (name "unconnected-(U6-P0_5-Pad16)") (class "Default")
      (node (ref "U6") (pin "16") (pinfunction "P0_5_16") (pintype "passive"))
    )
    (net (code "65") (name "unconnected-(U6-P0_11-Pad30)") (class "Default")
      (node (ref "U6") (pin "30") (pinfunction "P0_11_30") (pintype "passive"))
    )
    (net (code "66") (name "unconnected-(U6-P1_2-Pad35)") (class "Default")
      (node (ref "U6") (pin "35") (pinfunction "P1_2_35") (pintype "passive"))
    )
    (net (code "67") (name "unconnected-(U6-P1_10-Pad29)") (class "Default")
      (node (ref "U6") (pin "29") (pinfunction "P1_10_29") (pintype "passive"))
    )
    (net (code "68") (name "unconnected-(U6-P1_11-Pad42)") (class "Default")
      (node (ref "U6") (pin "42") (pinfunction "P1_11_42") (pintype "passive"))
    )
    (net (code "69") (name "unconnected-(U6-P2_0-Pad2)") (class "Default")
      (node (ref "U6") (pin "2") (pinfunction "P2_0_2") (pintype "passive"))
    )
    (net (code "70") (name "unconnected-(U6-P2_1-Pad13)") (class "Default")
      (node (ref "U6") (pin "13") (pinfunction "P2_1_13") (pintype "passive"))
    )
    (net (code "71") (name "unconnected-(U6-P2_4-Pad19)") (class "Default")
      (node (ref "U6") (pin "19") (pinfunction "P2_4_19") (pintype "passive"))
    )
    (net (code "72") (name "unconnected-(U6-P2_5-Pad20)") (class "Default")
      (node (ref "U6") (pin "20") (pinfunction "P2_5_20") (pintype "passive"))
    )
    (net (code "73") (name "unconnected-(U6-P2_6-Pad1)") (class "Default")
      (node (ref "U6") (pin "1") (pinfunction "P2_6_1") (pintype "passive"))
    )
    (net (code "74") (name "unconnected-(U6-P2_8-Pad12)") (class "Default")
      (node (ref "U6") (pin "12") (pinfunction "P2_8_12") (pintype "passive"))
    )
    (net (code "75") (name "unconnected-(U6-P3_4-Pad18)") (class "Default")
      (node (ref "U6") (pin "18") (pinfunction "P3_4_18") (pintype "passive"))
    )
    (net (code "76") (name "unconnected-(U6-P3_5-Pad21)") (class "Default")
      (node (ref "U6") (pin "21") (pinfunction "P3_5_21") (pintype "passive"))
    )
    (net (code "77") (name "unconnected-(U6-XTALIN-Pad6)") (class "Default")
      (node (ref "U6") (pin "6") (pinfunction "XTALIN_6") (pintype "passive"))
    )
    (net (code "78") (name "unconnected-(U6-XTALOUT-Pad7)") (class "Default")
      (node (ref "U6") (pin "7") (pinfunction "XTALOUT_7") (pintype "passive"))
    )
    (net (code "79") (name "unconnected-(U7-P01-Pad18)") (class "Default")
      (node (ref "U7") (pin "18") (pinfunction "P01_18") (pintype "passive"))
    )
    (net (code "80") (name "unconnected-(U7-P04-Pad15)") (class "Default")
      (node (ref "U7") (pin "15") (pinfunction "P04_15") (pintype "passive"))
    )
    (net (code "81") (name "unconnected-(U7-P05-Pad14)") (class "Default")
      (node (ref "U7") (pin "14") (pinfunction "P05_14") (pintype "passive"))
    )
    (net (code "82") (name "unconnected-(U7-P06-Pad13)") (class "Default")
      (node (ref "U7") (pin "13") (pinfunction "P06_13") (pintype "passive"))
    )
    (net (code "83") (name "unconnected-(U7-P07-Pad12)") (class "Default")
      (node (ref "U7") (pin "12") (pinfunction "P07_12") (pintype "passive"))
    )
    (net (code "84") (name "unconnected-(U7-P11-Pad11)") (class "Default")
      (node (ref "U7") (pin "11") (pinfunction "P11_11") (pintype "passive"))
    )
    (net (code "85") (name "unconnected-(U7-P12-Pad10)") (class "Default")
      (node (ref "U7") (pin "10") (pinfunction "P12_10") (pintype "passive"))
    )
    (net (code "86") (name "unconnected-(U7-P17-Pad7)") (class "Default")
      (node (ref "U7") (pin "7") (pinfunction "P17_7") (pintype "passive"))
    )
    (net (code "87") (name "unconnected-(U7-P20-Pad6)") (class "Default")
      (node (ref "U7") (pin "6") (pinfunction "P20_6") (pintype "passive"))
    )
    (net (code "88") (name "unconnected-(U7-P21-Pad4)") (class "Default")
      (node (ref "U7") (pin "4") (pinfunction "P21_4") (pintype "passive"))
    )
    (net (code "89") (name "unconnected-(U7-P22-Pad3)") (class "Default")
      (node (ref "U7") (pin "3") (pinfunction "P22_3") (pintype "passive"))
    )
    (net (code "90") (name "unconnected-(U7-U+-Pad8)") (class "Default")
      (node (ref "U7") (pin "8") (pinfunction "U+_8") (pintype "passive"))
    )
    (net (code "91") (name "unconnected-(U7-U--Pad9)") (class "Default")
      (node (ref "U7") (pin "9") (pinfunction "U-_9") (pintype "passive"))
    )
  )
)
